# H01.net
KiCad netlist of a schematic drawn in EAGLE
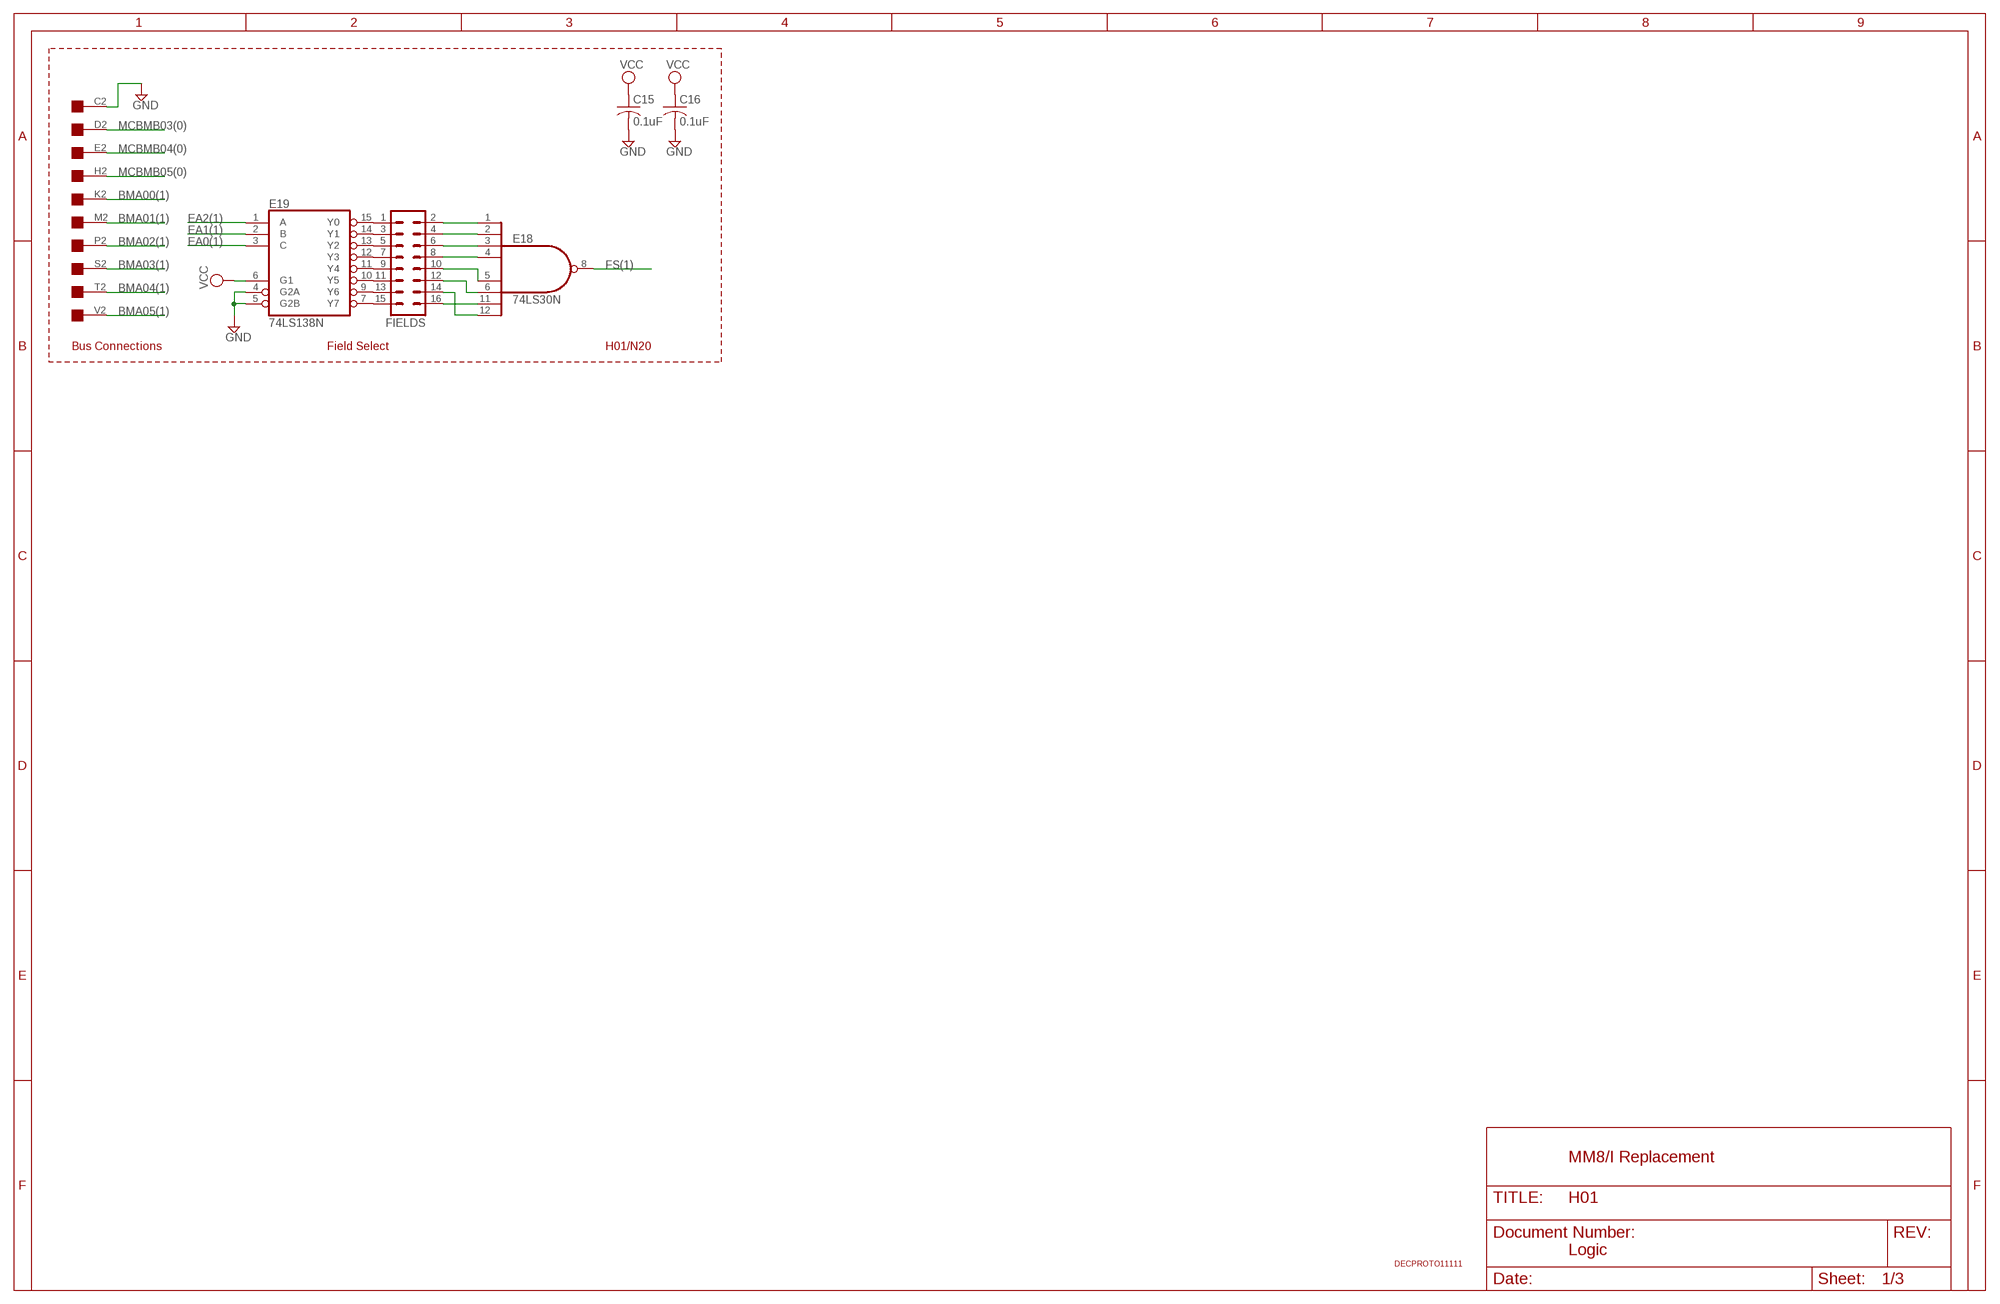
[diagram p0: schematic, sheet 1]
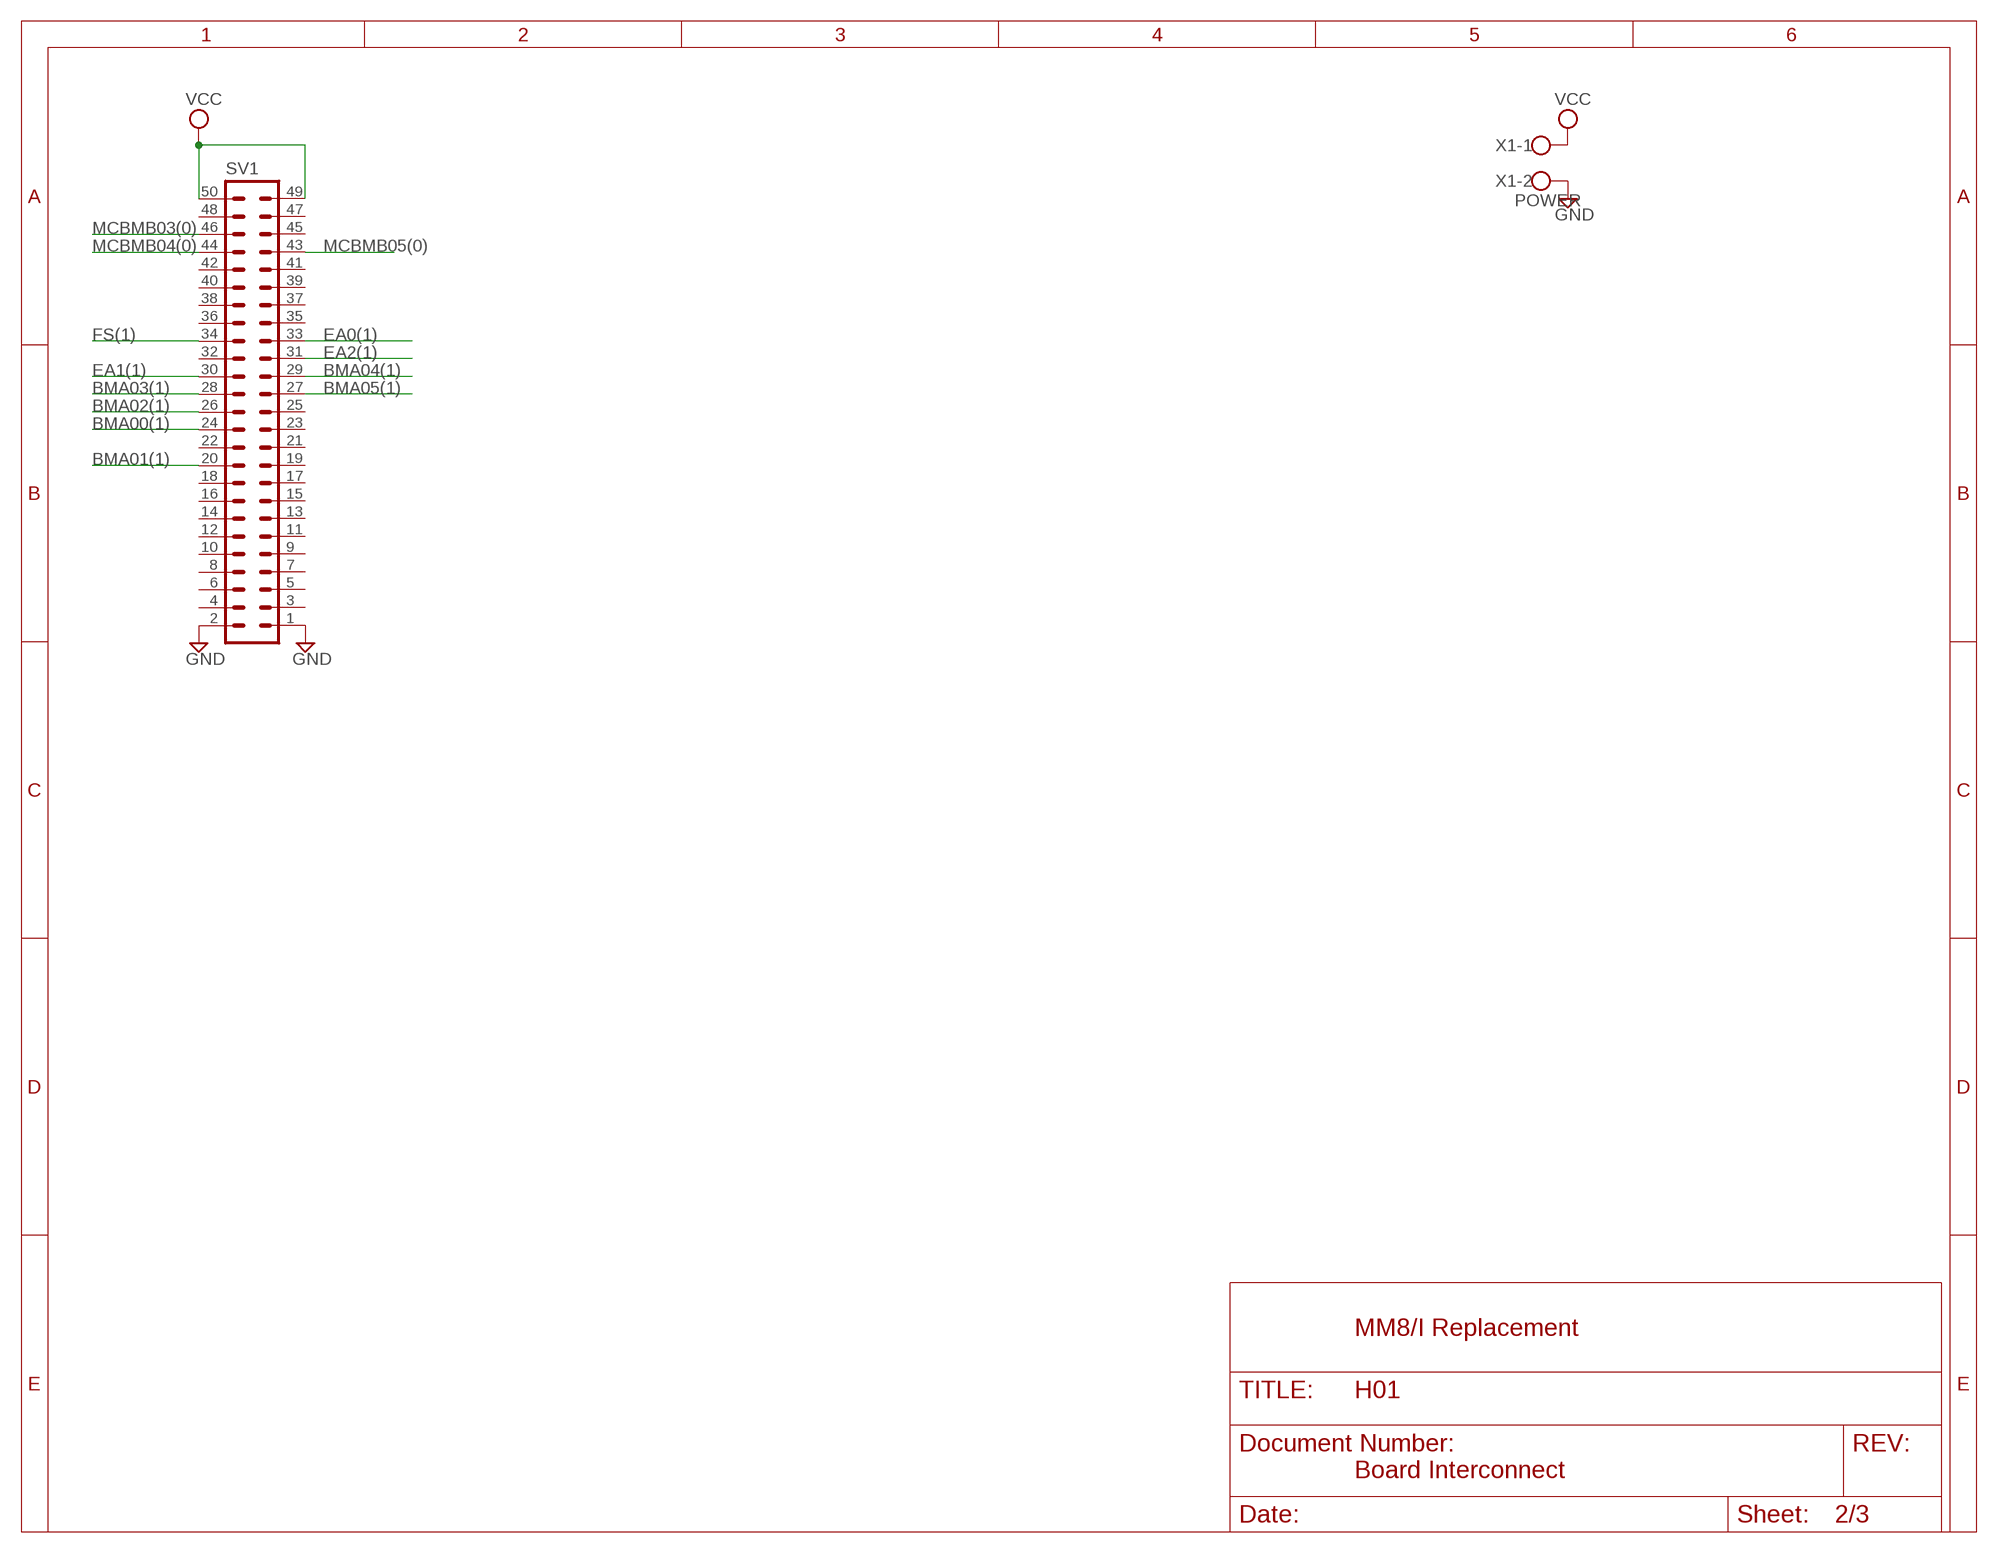
[diagram p1: schematic, sheet 2]
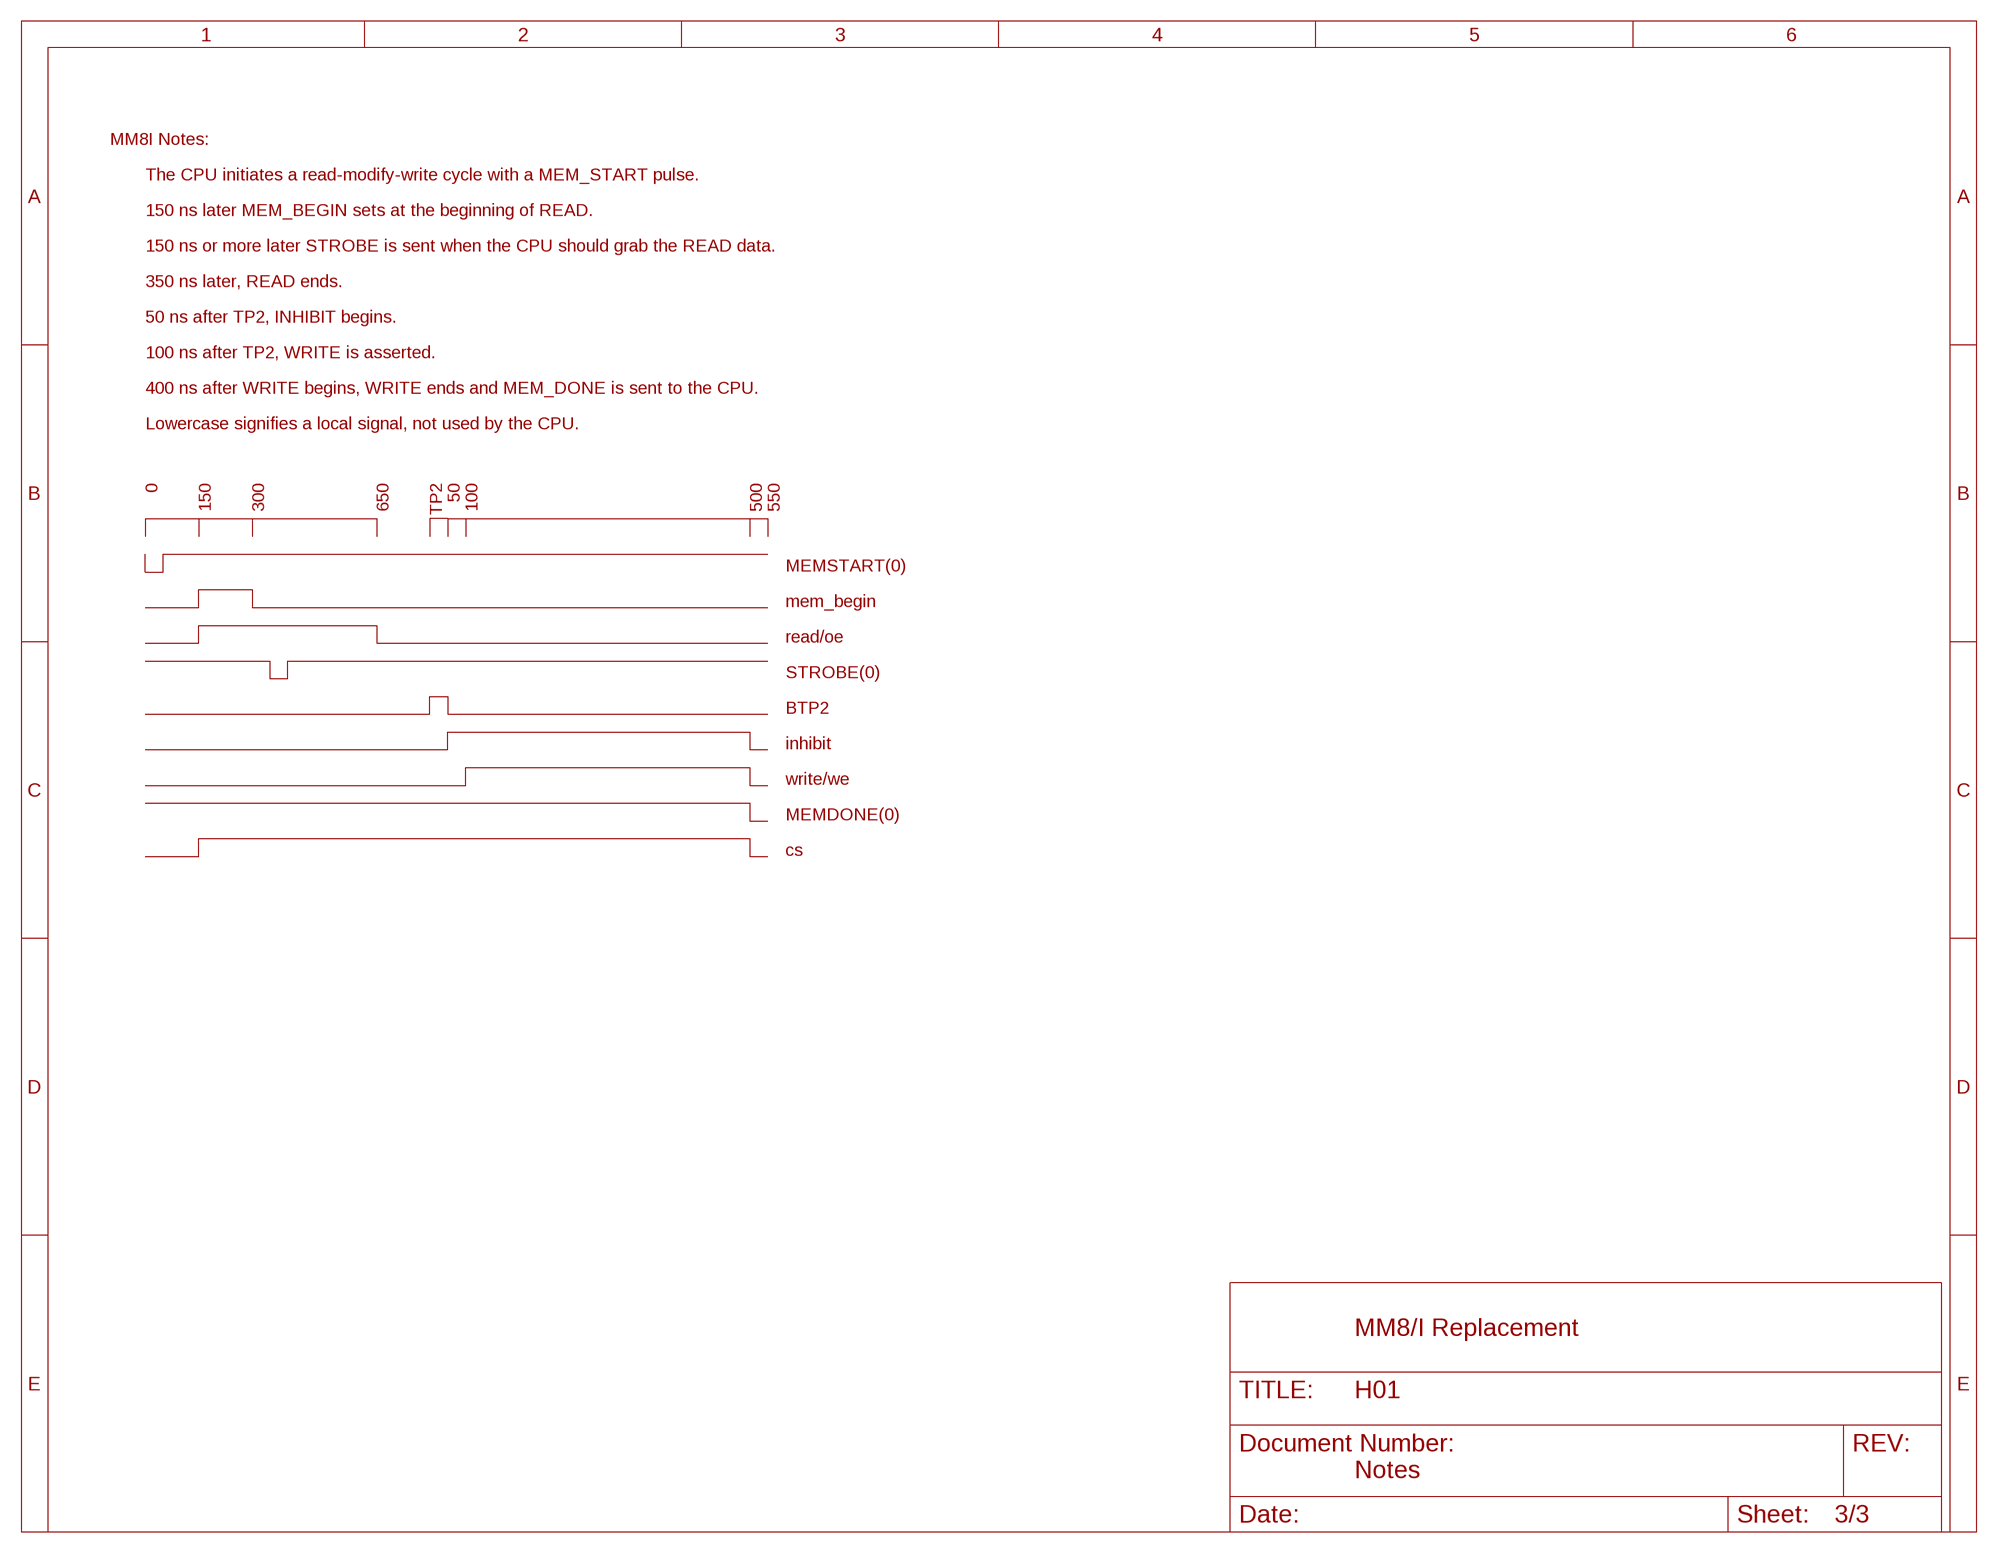
[diagram p2: schematic, sheet 3]

(export (version "E")
  (design (tool "Eeschema 10.0.6"))
  (components
    (comp (ref "SV1")
      (value "ML50L")
      (footprint "eagle-import:ML50L")
      (libsource (lib "eagle-import") (part "ML50L"))
    )
    (comp (ref "X1")
      (value "POWER")
      (footprint "eagle-import:W237-102")
      (fields (field (name "MPN") "237-102"))
      (libsource (lib "eagle-import") (part "W237-102"))
    )
    (comp (ref "C15")
      (value "0.1uF")
      (footprint "eagle-import:C050-025X075")
      (libsource (lib "eagle-import") (part "C-US050-025X075"))
    )
    (comp (ref "C16")
      (value "0.1uF")
      (footprint "eagle-import:C050-025X075")
      (libsource (lib "eagle-import") (part "C-US050-025X075"))
    )
    (comp (ref "E18")
      (value "74LS30N")
      (footprint "eagle-import:DIL14")
      (libsource (lib "eagle-import") (part "7430NLS"))
    )
    (comp (ref "E19")
      (value "74LS138N")
      (footprint "eagle-import:DIL16")
      (libsource (lib "eagle-import") (part "74138NLS"))
    )
    (comp (ref "FIELDS")
      (value "MA08-2")
      (footprint "eagle-import:MA08-2")
      (libsource (lib "eagle-import") (part "MA08-2"))
    )
    (comp (ref "H01")
      (value "EDGE-1")
      (footprint "eagle-import:EDGE-CON1")
      (libsource (lib "eagle-import") (part "EDGE-1"))
    )
    (comp (ref "U$6")
      (value "DECPROTO11111")
      (footprint "eagle-import:DECPROTO11111")
      (libsource (lib "eagle-import") (part "DECPROTO11111"))
    )
  )
  (nets
    (net (code "1") (name "BMA00(1)") (class "Default")
      (node (ref "H01") (pin "K2") (pinfunction "1_K2") (pintype "bidirectional"))
      (node (ref "SV1") (pin "24") (pinfunction "24_24") (pintype "passive"))
    )
    (net (code "2") (name "BMA01(1)") (class "Default")
      (node (ref "H01") (pin "M2") (pinfunction "1_M2") (pintype "bidirectional"))
      (node (ref "SV1") (pin "20") (pinfunction "20_20") (pintype "passive"))
    )
    (net (code "3") (name "BMA02(1)") (class "Default")
      (node (ref "H01") (pin "P2") (pinfunction "1_P2") (pintype "bidirectional"))
      (node (ref "SV1") (pin "26") (pinfunction "26_26") (pintype "passive"))
    )
    (net (code "4") (name "BMA03(1)") (class "Default")
      (node (ref "H01") (pin "S2") (pinfunction "1_S2") (pintype "bidirectional"))
      (node (ref "SV1") (pin "28") (pinfunction "28_28") (pintype "passive"))
    )
    (net (code "5") (name "BMA04(1)") (class "Default")
      (node (ref "H01") (pin "T2") (pinfunction "1_T2") (pintype "bidirectional"))
      (node (ref "SV1") (pin "29") (pinfunction "29_29") (pintype "passive"))
    )
    (net (code "6") (name "BMA05(1)") (class "Default")
      (node (ref "H01") (pin "V2") (pinfunction "1_V2") (pintype "bidirectional"))
      (node (ref "SV1") (pin "27") (pinfunction "27_27") (pintype "passive"))
    )
    (net (code "7") (name "EA0(1)") (class "Default")
      (node (ref "E19") (pin "3") (pinfunction "C_3") (pintype "input"))
      (node (ref "SV1") (pin "33") (pinfunction "33_33") (pintype "passive"))
    )
    (net (code "8") (name "EA1(1)") (class "Default")
      (node (ref "E19") (pin "2") (pinfunction "B_2") (pintype "input"))
      (node (ref "SV1") (pin "30") (pinfunction "30_30") (pintype "passive"))
    )
    (net (code "9") (name "EA2(1)") (class "Default")
      (node (ref "E19") (pin "1") (pinfunction "A_1") (pintype "input"))
      (node (ref "SV1") (pin "31") (pinfunction "31_31") (pintype "passive"))
    )
    (net (code "10") (name "FS(1)") (class "Default")
      (node (ref "E18") (pin "8") (pinfunction "O_8") (pintype "output"))
      (node (ref "SV1") (pin "34") (pinfunction "34_34") (pintype "passive"))
    )
    (net (code "11") (name "GND") (class "Default")
      (node (ref "C15") (pin "2") (pinfunction "2_2") (pintype "passive"))
      (node (ref "C16") (pin "2") (pinfunction "2_2") (pintype "passive"))
      (node (ref "E19") (pin "4") (pinfunction "G2A_4") (pintype "input"))
      (node (ref "E19") (pin "5") (pinfunction "G2B_5") (pintype "input"))
      (node (ref "H01") (pin "C2") (pinfunction "1_C2") (pintype "bidirectional"))
      (node (ref "SV1") (pin "1") (pinfunction "1_1") (pintype "passive"))
      (node (ref "SV1") (pin "2") (pinfunction "2_2") (pintype "passive"))
      (node (ref "X1") (pin "2") (pinfunction "KL_2") (pintype "passive"))
    )
    (net (code "12") (name "MCBMB03(0)") (class "Default")
      (node (ref "H01") (pin "D2") (pinfunction "1_D2") (pintype "bidirectional"))
      (node (ref "SV1") (pin "46") (pinfunction "46_46") (pintype "passive"))
    )
    (net (code "13") (name "MCBMB04(0)") (class "Default")
      (node (ref "H01") (pin "E2") (pinfunction "1_E2") (pintype "bidirectional"))
      (node (ref "SV1") (pin "44") (pinfunction "44_44") (pintype "passive"))
    )
    (net (code "14") (name "MCBMB05(0)") (class "Default")
      (node (ref "H01") (pin "H2") (pinfunction "1_H2") (pintype "bidirectional"))
      (node (ref "SV1") (pin "43") (pinfunction "43_43") (pintype "passive"))
    )
    (net (code "15") (name "Net-(E18A-I0)") (class "Default")
      (node (ref "E18") (pin "1") (pinfunction "I0_1") (pintype "input"))
      (node (ref "FIELDS") (pin "2") (pinfunction "2_2") (pintype "passive"))
    )
    (net (code "16") (name "Net-(E18A-I1)") (class "Default")
      (node (ref "E18") (pin "2") (pinfunction "I1_2") (pintype "input"))
      (node (ref "FIELDS") (pin "4") (pinfunction "4_4") (pintype "passive"))
    )
    (net (code "17") (name "Net-(E18A-I2)") (class "Default")
      (node (ref "E18") (pin "3") (pinfunction "I2_3") (pintype "input"))
      (node (ref "FIELDS") (pin "6") (pinfunction "6_6") (pintype "passive"))
    )
    (net (code "18") (name "Net-(E18A-I3)") (class "Default")
      (node (ref "E18") (pin "4") (pinfunction "I3_4") (pintype "input"))
      (node (ref "FIELDS") (pin "8") (pinfunction "8_8") (pintype "passive"))
    )
    (net (code "19") (name "Net-(E18A-I4)") (class "Default")
      (node (ref "E18") (pin "5") (pinfunction "I4_5") (pintype "input"))
      (node (ref "FIELDS") (pin "10") (pinfunction "10_10") (pintype "passive"))
    )
    (net (code "20") (name "Net-(E18A-I5)") (class "Default")
      (node (ref "E18") (pin "6") (pinfunction "I5_6") (pintype "input"))
      (node (ref "FIELDS") (pin "12") (pinfunction "12_12") (pintype "passive"))
    )
    (net (code "21") (name "Net-(E18A-I6)") (class "Default")
      (node (ref "E18") (pin "11") (pinfunction "I6_11") (pintype "input"))
      (node (ref "FIELDS") (pin "16") (pinfunction "16_16") (pintype "passive"))
    )
    (net (code "22") (name "Net-(E18A-I7)") (class "Default")
      (node (ref "E18") (pin "12") (pinfunction "I7_12") (pintype "input"))
      (node (ref "FIELDS") (pin "14") (pinfunction "14_14") (pintype "passive"))
    )
    (net (code "23") (name "Net-(E19A-Y0)") (class "Default")
      (node (ref "E19") (pin "15") (pinfunction "Y0_15") (pintype "output"))
      (node (ref "FIELDS") (pin "1") (pinfunction "1_1") (pintype "passive"))
    )
    (net (code "24") (name "Net-(E19A-Y1)") (class "Default")
      (node (ref "E19") (pin "14") (pinfunction "Y1_14") (pintype "output"))
      (node (ref "FIELDS") (pin "3") (pinfunction "3_3") (pintype "passive"))
    )
    (net (code "25") (name "Net-(E19A-Y2)") (class "Default")
      (node (ref "E19") (pin "13") (pinfunction "Y2_13") (pintype "output"))
      (node (ref "FIELDS") (pin "5") (pinfunction "5_5") (pintype "passive"))
    )
    (net (code "26") (name "Net-(E19A-Y3)") (class "Default")
      (node (ref "E19") (pin "12") (pinfunction "Y3_12") (pintype "output"))
      (node (ref "FIELDS") (pin "7") (pinfunction "7_7") (pintype "passive"))
    )
    (net (code "27") (name "Net-(E19A-Y4)") (class "Default")
      (node (ref "E19") (pin "11") (pinfunction "Y4_11") (pintype "output"))
      (node (ref "FIELDS") (pin "9") (pinfunction "9_9") (pintype "passive"))
    )
    (net (code "28") (name "Net-(E19A-Y5)") (class "Default")
      (node (ref "E19") (pin "10") (pinfunction "Y5_10") (pintype "output"))
      (node (ref "FIELDS") (pin "11") (pinfunction "11_11") (pintype "passive"))
    )
    (net (code "29") (name "Net-(E19A-Y6)") (class "Default")
      (node (ref "E19") (pin "9") (pinfunction "Y6_9") (pintype "output"))
      (node (ref "FIELDS") (pin "13") (pinfunction "13_13") (pintype "passive"))
    )
    (net (code "30") (name "Net-(E19A-Y7)") (class "Default")
      (node (ref "E19") (pin "7") (pinfunction "Y7_7") (pintype "output"))
      (node (ref "FIELDS") (pin "15") (pinfunction "15_15") (pintype "passive"))
    )
    (net (code "31") (name "VCC") (class "Default")
      (node (ref "C15") (pin "1") (pinfunction "1_1") (pintype "passive"))
      (node (ref "C16") (pin "1") (pinfunction "1_1") (pintype "passive"))
      (node (ref "E19") (pin "6") (pinfunction "G1_6") (pintype "input"))
      (node (ref "SV1") (pin "49") (pinfunction "49_49") (pintype "passive"))
      (node (ref "SV1") (pin "50") (pinfunction "50_50") (pintype "passive"))
      (node (ref "X1") (pin "1") (pinfunction "KL_1") (pintype "passive"))
    )
    (net (code "32") (name "unconnected-(SV1-Pad3)") (class "Default")
      (node (ref "SV1") (pin "3") (pinfunction "3_3") (pintype "passive"))
    )
    (net (code "33") (name "unconnected-(SV1-Pad4)") (class "Default")
      (node (ref "SV1") (pin "4") (pinfunction "4_4") (pintype "passive"))
    )
    (net (code "34") (name "unconnected-(SV1-Pad5)") (class "Default")
      (node (ref "SV1") (pin "5") (pinfunction "5_5") (pintype "passive"))
    )
    (net (code "35") (name "unconnected-(SV1-Pad6)") (class "Default")
      (node (ref "SV1") (pin "6") (pinfunction "6_6") (pintype "passive"))
    )
    (net (code "36") (name "unconnected-(SV1-Pad7)") (class "Default")
      (node (ref "SV1") (pin "7") (pinfunction "7_7") (pintype "passive"))
    )
    (net (code "37") (name "unconnected-(SV1-Pad8)") (class "Default")
      (node (ref "SV1") (pin "8") (pinfunction "8_8") (pintype "passive"))
    )
    (net (code "38") (name "unconnected-(SV1-Pad9)") (class "Default")
      (node (ref "SV1") (pin "9") (pinfunction "9_9") (pintype "passive"))
    )
    (net (code "39") (name "unconnected-(SV1-Pad10)") (class "Default")
      (node (ref "SV1") (pin "10") (pinfunction "10_10") (pintype "passive"))
    )
    (net (code "40") (name "unconnected-(SV1-Pad11)") (class "Default")
      (node (ref "SV1") (pin "11") (pinfunction "11_11") (pintype "passive"))
    )
    (net (code "41") (name "unconnected-(SV1-Pad12)") (class "Default")
      (node (ref "SV1") (pin "12") (pinfunction "12_12") (pintype "passive"))
    )
    (net (code "42") (name "unconnected-(SV1-Pad13)") (class "Default")
      (node (ref "SV1") (pin "13") (pinfunction "13_13") (pintype "passive"))
    )
    (net (code "43") (name "unconnected-(SV1-Pad14)") (class "Default")
      (node (ref "SV1") (pin "14") (pinfunction "14_14") (pintype "passive"))
    )
    (net (code "44") (name "unconnected-(SV1-Pad15)") (class "Default")
      (node (ref "SV1") (pin "15") (pinfunction "15_15") (pintype "passive"))
    )
    (net (code "45") (name "unconnected-(SV1-Pad16)") (class "Default")
      (node (ref "SV1") (pin "16") (pinfunction "16_16") (pintype "passive"))
    )
    (net (code "46") (name "unconnected-(SV1-Pad17)") (class "Default")
      (node (ref "SV1") (pin "17") (pinfunction "17_17") (pintype "passive"))
    )
    (net (code "47") (name "unconnected-(SV1-Pad18)") (class "Default")
      (node (ref "SV1") (pin "18") (pinfunction "18_18") (pintype "passive"))
    )
    (net (code "48") (name "unconnected-(SV1-Pad19)") (class "Default")
      (node (ref "SV1") (pin "19") (pinfunction "19_19") (pintype "passive"))
    )
    (net (code "49") (name "unconnected-(SV1-Pad21)") (class "Default")
      (node (ref "SV1") (pin "21") (pinfunction "21_21") (pintype "passive"))
    )
    (net (code "50") (name "unconnected-(SV1-Pad22)") (class "Default")
      (node (ref "SV1") (pin "22") (pinfunction "22_22") (pintype "passive"))
    )
    (net (code "51") (name "unconnected-(SV1-Pad23)") (class "Default")
      (node (ref "SV1") (pin "23") (pinfunction "23_23") (pintype "passive"))
    )
    (net (code "52") (name "unconnected-(SV1-Pad25)") (class "Default")
      (node (ref "SV1") (pin "25") (pinfunction "25_25") (pintype "passive"))
    )
    (net (code "53") (name "unconnected-(SV1-Pad32)") (class "Default")
      (node (ref "SV1") (pin "32") (pinfunction "32_32") (pintype "passive"))
    )
    (net (code "54") (name "unconnected-(SV1-Pad35)") (class "Default")
      (node (ref "SV1") (pin "35") (pinfunction "35_35") (pintype "passive"))
    )
    (net (code "55") (name "unconnected-(SV1-Pad36)") (class "Default")
      (node (ref "SV1") (pin "36") (pinfunction "36_36") (pintype "passive"))
    )
    (net (code "56") (name "unconnected-(SV1-Pad37)") (class "Default")
      (node (ref "SV1") (pin "37") (pinfunction "37_37") (pintype "passive"))
    )
    (net (code "57") (name "unconnected-(SV1-Pad38)") (class "Default")
      (node (ref "SV1") (pin "38") (pinfunction "38_38") (pintype "passive"))
    )
    (net (code "58") (name "unconnected-(SV1-Pad39)") (class "Default")
      (node (ref "SV1") (pin "39") (pinfunction "39_39") (pintype "passive"))
    )
    (net (code "59") (name "unconnected-(SV1-Pad40)") (class "Default")
      (node (ref "SV1") (pin "40") (pinfunction "40_40") (pintype "passive"))
    )
    (net (code "60") (name "unconnected-(SV1-Pad41)") (class "Default")
      (node (ref "SV1") (pin "41") (pinfunction "41_41") (pintype "passive"))
    )
    (net (code "61") (name "unconnected-(SV1-Pad42)") (class "Default")
      (node (ref "SV1") (pin "42") (pinfunction "42_42") (pintype "passive"))
    )
    (net (code "62") (name "unconnected-(SV1-Pad45)") (class "Default")
      (node (ref "SV1") (pin "45") (pinfunction "45_45") (pintype "passive"))
    )
    (net (code "63") (name "unconnected-(SV1-Pad47)") (class "Default")
      (node (ref "SV1") (pin "47") (pinfunction "47_47") (pintype "passive"))
    )
    (net (code "64") (name "unconnected-(SV1-Pad48)") (class "Default")
      (node (ref "SV1") (pin "48") (pinfunction "48_48") (pintype "passive"))
    )
  )
)
